# led_panel.net
KiCad netlist of a schematic drawn in EAGLE
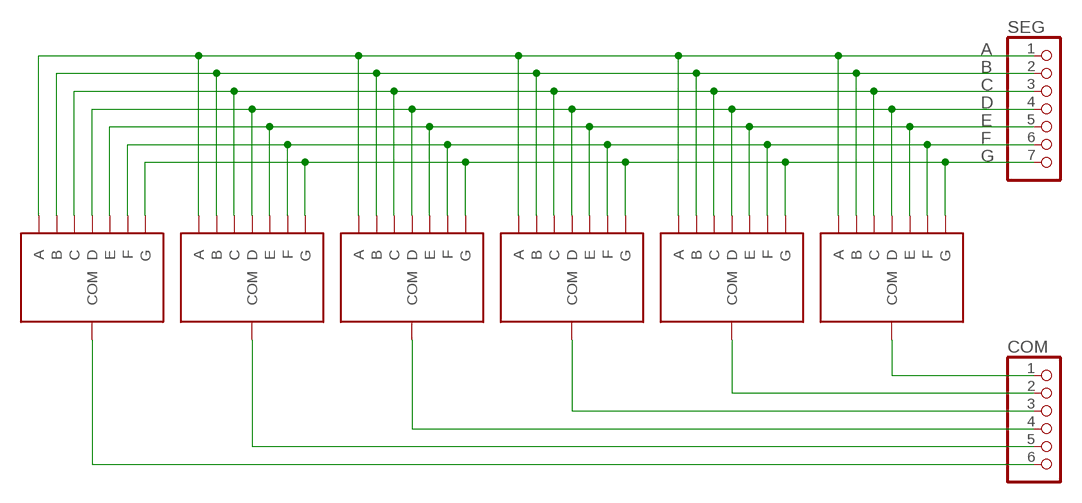
[diagram p0: schematic, sheet 1]

(export (version "E")
  (design (tool "Eeschema 10.0.6"))
  (components
    (comp (ref "COM")
      (value "PINHD-1X6")
      (footprint "eagle-import:1X06")
      (libsource (lib "eagle-import") (part "PINHD-1X6"))
    )
    (comp (ref "SEG")
      (value "PINHD-1X7")
      (footprint "eagle-import:1X07")
      (libsource (lib "eagle-import") (part "PINHD-1X7"))
    )
    (comp (ref "U$1")
      (value "7SEGMENTLED")
      (footprint "eagle-import:7SEGMENTLED")
      (libsource (lib "eagle-import") (part "7SEGMENTLED"))
    )
    (comp (ref "U$2")
      (value "7SEGMENTLED")
      (footprint "eagle-import:7SEGMENTLED")
      (libsource (lib "eagle-import") (part "7SEGMENTLED"))
    )
    (comp (ref "U$3")
      (value "7SEGMENTLED")
      (footprint "eagle-import:7SEGMENTLED")
      (libsource (lib "eagle-import") (part "7SEGMENTLED"))
    )
    (comp (ref "U$4")
      (value "7SEGMENTLED")
      (footprint "eagle-import:7SEGMENTLED")
      (libsource (lib "eagle-import") (part "7SEGMENTLED"))
    )
    (comp (ref "U$5")
      (value "7SEGMENTLED")
      (footprint "eagle-import:7SEGMENTLED")
      (libsource (lib "eagle-import") (part "7SEGMENTLED"))
    )
    (comp (ref "U$6")
      (value "7SEGMENTLED")
      (footprint "eagle-import:7SEGMENTLED")
      (libsource (lib "eagle-import") (part "7SEGMENTLED"))
    )
  )
  (nets
    (net (code "1") (name "/A") (class "Default")
      (node (ref "SEG") (pin "1") (pinfunction "1_1") (pintype "passive"))
      (node (ref "U$1") (pin "P$4") (pinfunction "A_P$4") (pintype "bidirectional"))
      (node (ref "U$2") (pin "P$4") (pinfunction "A_P$4") (pintype "bidirectional"))
      (node (ref "U$3") (pin "P$4") (pinfunction "A_P$4") (pintype "bidirectional"))
      (node (ref "U$4") (pin "P$4") (pinfunction "A_P$4") (pintype "bidirectional"))
      (node (ref "U$5") (pin "P$4") (pinfunction "A_P$4") (pintype "bidirectional"))
      (node (ref "U$6") (pin "P$4") (pinfunction "A_P$4") (pintype "bidirectional"))
    )
    (net (code "2") (name "/B") (class "Default")
      (node (ref "SEG") (pin "2") (pinfunction "2_2") (pintype "passive"))
      (node (ref "U$1") (pin "P$5") (pinfunction "B_P$5") (pintype "bidirectional"))
      (node (ref "U$2") (pin "P$5") (pinfunction "B_P$5") (pintype "bidirectional"))
      (node (ref "U$3") (pin "P$5") (pinfunction "B_P$5") (pintype "bidirectional"))
      (node (ref "U$4") (pin "P$5") (pinfunction "B_P$5") (pintype "bidirectional"))
      (node (ref "U$5") (pin "P$5") (pinfunction "B_P$5") (pintype "bidirectional"))
      (node (ref "U$6") (pin "P$5") (pinfunction "B_P$5") (pintype "bidirectional"))
    )
    (net (code "3") (name "/C") (class "Default")
      (node (ref "SEG") (pin "3") (pinfunction "3_3") (pintype "passive"))
      (node (ref "U$1") (pin "P$9") (pinfunction "C_P$9") (pintype "bidirectional"))
      (node (ref "U$2") (pin "P$9") (pinfunction "C_P$9") (pintype "bidirectional"))
      (node (ref "U$3") (pin "P$9") (pinfunction "C_P$9") (pintype "bidirectional"))
      (node (ref "U$4") (pin "P$9") (pinfunction "C_P$9") (pintype "bidirectional"))
      (node (ref "U$5") (pin "P$9") (pinfunction "C_P$9") (pintype "bidirectional"))
      (node (ref "U$6") (pin "P$9") (pinfunction "C_P$9") (pintype "bidirectional"))
    )
    (net (code "4") (name "/D") (class "Default")
      (node (ref "SEG") (pin "4") (pinfunction "4_4") (pintype "passive"))
      (node (ref "U$1") (pin "P$7") (pinfunction "D_P$7") (pintype "bidirectional"))
      (node (ref "U$2") (pin "P$7") (pinfunction "D_P$7") (pintype "bidirectional"))
      (node (ref "U$3") (pin "P$7") (pinfunction "D_P$7") (pintype "bidirectional"))
      (node (ref "U$4") (pin "P$7") (pinfunction "D_P$7") (pintype "bidirectional"))
      (node (ref "U$5") (pin "P$7") (pinfunction "D_P$7") (pintype "bidirectional"))
      (node (ref "U$6") (pin "P$7") (pinfunction "D_P$7") (pintype "bidirectional"))
    )
    (net (code "5") (name "/E") (class "Default")
      (node (ref "SEG") (pin "5") (pinfunction "5_5") (pintype "passive"))
      (node (ref "U$1") (pin "P$6") (pinfunction "E_P$6") (pintype "bidirectional"))
      (node (ref "U$2") (pin "P$6") (pinfunction "E_P$6") (pintype "bidirectional"))
      (node (ref "U$3") (pin "P$6") (pinfunction "E_P$6") (pintype "bidirectional"))
      (node (ref "U$4") (pin "P$6") (pinfunction "E_P$6") (pintype "bidirectional"))
      (node (ref "U$5") (pin "P$6") (pinfunction "E_P$6") (pintype "bidirectional"))
      (node (ref "U$6") (pin "P$6") (pinfunction "E_P$6") (pintype "bidirectional"))
    )
    (net (code "6") (name "/F") (class "Default")
      (node (ref "SEG") (pin "6") (pinfunction "6_6") (pintype "passive"))
      (node (ref "U$1") (pin "P$2") (pinfunction "F_P$2") (pintype "bidirectional"))
      (node (ref "U$2") (pin "P$2") (pinfunction "F_P$2") (pintype "bidirectional"))
      (node (ref "U$3") (pin "P$2") (pinfunction "F_P$2") (pintype "bidirectional"))
      (node (ref "U$4") (pin "P$2") (pinfunction "F_P$2") (pintype "bidirectional"))
      (node (ref "U$5") (pin "P$2") (pinfunction "F_P$2") (pintype "bidirectional"))
      (node (ref "U$6") (pin "P$2") (pinfunction "F_P$2") (pintype "bidirectional"))
    )
    (net (code "7") (name "/G") (class "Default")
      (node (ref "SEG") (pin "7") (pinfunction "7_7") (pintype "passive"))
      (node (ref "U$1") (pin "P$1") (pinfunction "G_P$1") (pintype "bidirectional"))
      (node (ref "U$2") (pin "P$1") (pinfunction "G_P$1") (pintype "bidirectional"))
      (node (ref "U$3") (pin "P$1") (pinfunction "G_P$1") (pintype "bidirectional"))
      (node (ref "U$4") (pin "P$1") (pinfunction "G_P$1") (pintype "bidirectional"))
      (node (ref "U$5") (pin "P$1") (pinfunction "G_P$1") (pintype "bidirectional"))
      (node (ref "U$6") (pin "P$1") (pinfunction "G_P$1") (pintype "bidirectional"))
    )
    (net (code "8") (name "Net-(COM-Pad1)") (class "Default")
      (node (ref "COM") (pin "1") (pinfunction "1_1") (pintype "passive"))
      (node (ref "U$6") (pin "P$10") (pinfunction "COM_P$10") (pintype "bidirectional"))
      (node (ref "U$6") (pin "P$3") (pinfunction "COM_P$3") (pintype "bidirectional"))
      (node (ref "U$6") (pin "P$8") (pinfunction "COM_P$8") (pintype "bidirectional"))
    )
    (net (code "9") (name "Net-(COM-Pad2)") (class "Default")
      (node (ref "COM") (pin "2") (pinfunction "2_2") (pintype "passive"))
      (node (ref "U$5") (pin "P$10") (pinfunction "COM_P$10") (pintype "bidirectional"))
      (node (ref "U$5") (pin "P$3") (pinfunction "COM_P$3") (pintype "bidirectional"))
      (node (ref "U$5") (pin "P$8") (pinfunction "COM_P$8") (pintype "bidirectional"))
    )
    (net (code "10") (name "Net-(COM-Pad3)") (class "Default")
      (node (ref "COM") (pin "3") (pinfunction "3_3") (pintype "passive"))
      (node (ref "U$4") (pin "P$10") (pinfunction "COM_P$10") (pintype "bidirectional"))
      (node (ref "U$4") (pin "P$3") (pinfunction "COM_P$3") (pintype "bidirectional"))
      (node (ref "U$4") (pin "P$8") (pinfunction "COM_P$8") (pintype "bidirectional"))
    )
    (net (code "11") (name "Net-(COM-Pad4)") (class "Default")
      (node (ref "COM") (pin "4") (pinfunction "4_4") (pintype "passive"))
      (node (ref "U$3") (pin "P$10") (pinfunction "COM_P$10") (pintype "bidirectional"))
      (node (ref "U$3") (pin "P$3") (pinfunction "COM_P$3") (pintype "bidirectional"))
      (node (ref "U$3") (pin "P$8") (pinfunction "COM_P$8") (pintype "bidirectional"))
    )
    (net (code "12") (name "Net-(COM-Pad5)") (class "Default")
      (node (ref "COM") (pin "5") (pinfunction "5_5") (pintype "passive"))
      (node (ref "U$2") (pin "P$10") (pinfunction "COM_P$10") (pintype "bidirectional"))
      (node (ref "U$2") (pin "P$3") (pinfunction "COM_P$3") (pintype "bidirectional"))
      (node (ref "U$2") (pin "P$8") (pinfunction "COM_P$8") (pintype "bidirectional"))
    )
    (net (code "13") (name "Net-(COM-Pad6)") (class "Default")
      (node (ref "COM") (pin "6") (pinfunction "6_6") (pintype "passive"))
      (node (ref "U$1") (pin "P$10") (pinfunction "COM_P$10") (pintype "bidirectional"))
      (node (ref "U$1") (pin "P$3") (pinfunction "COM_P$3") (pintype "bidirectional"))
      (node (ref "U$1") (pin "P$8") (pinfunction "COM_P$8") (pintype "bidirectional"))
    )
  )
)
